# Sheet1.net
KiCad netlist of a schematic drawn in Altium Designer
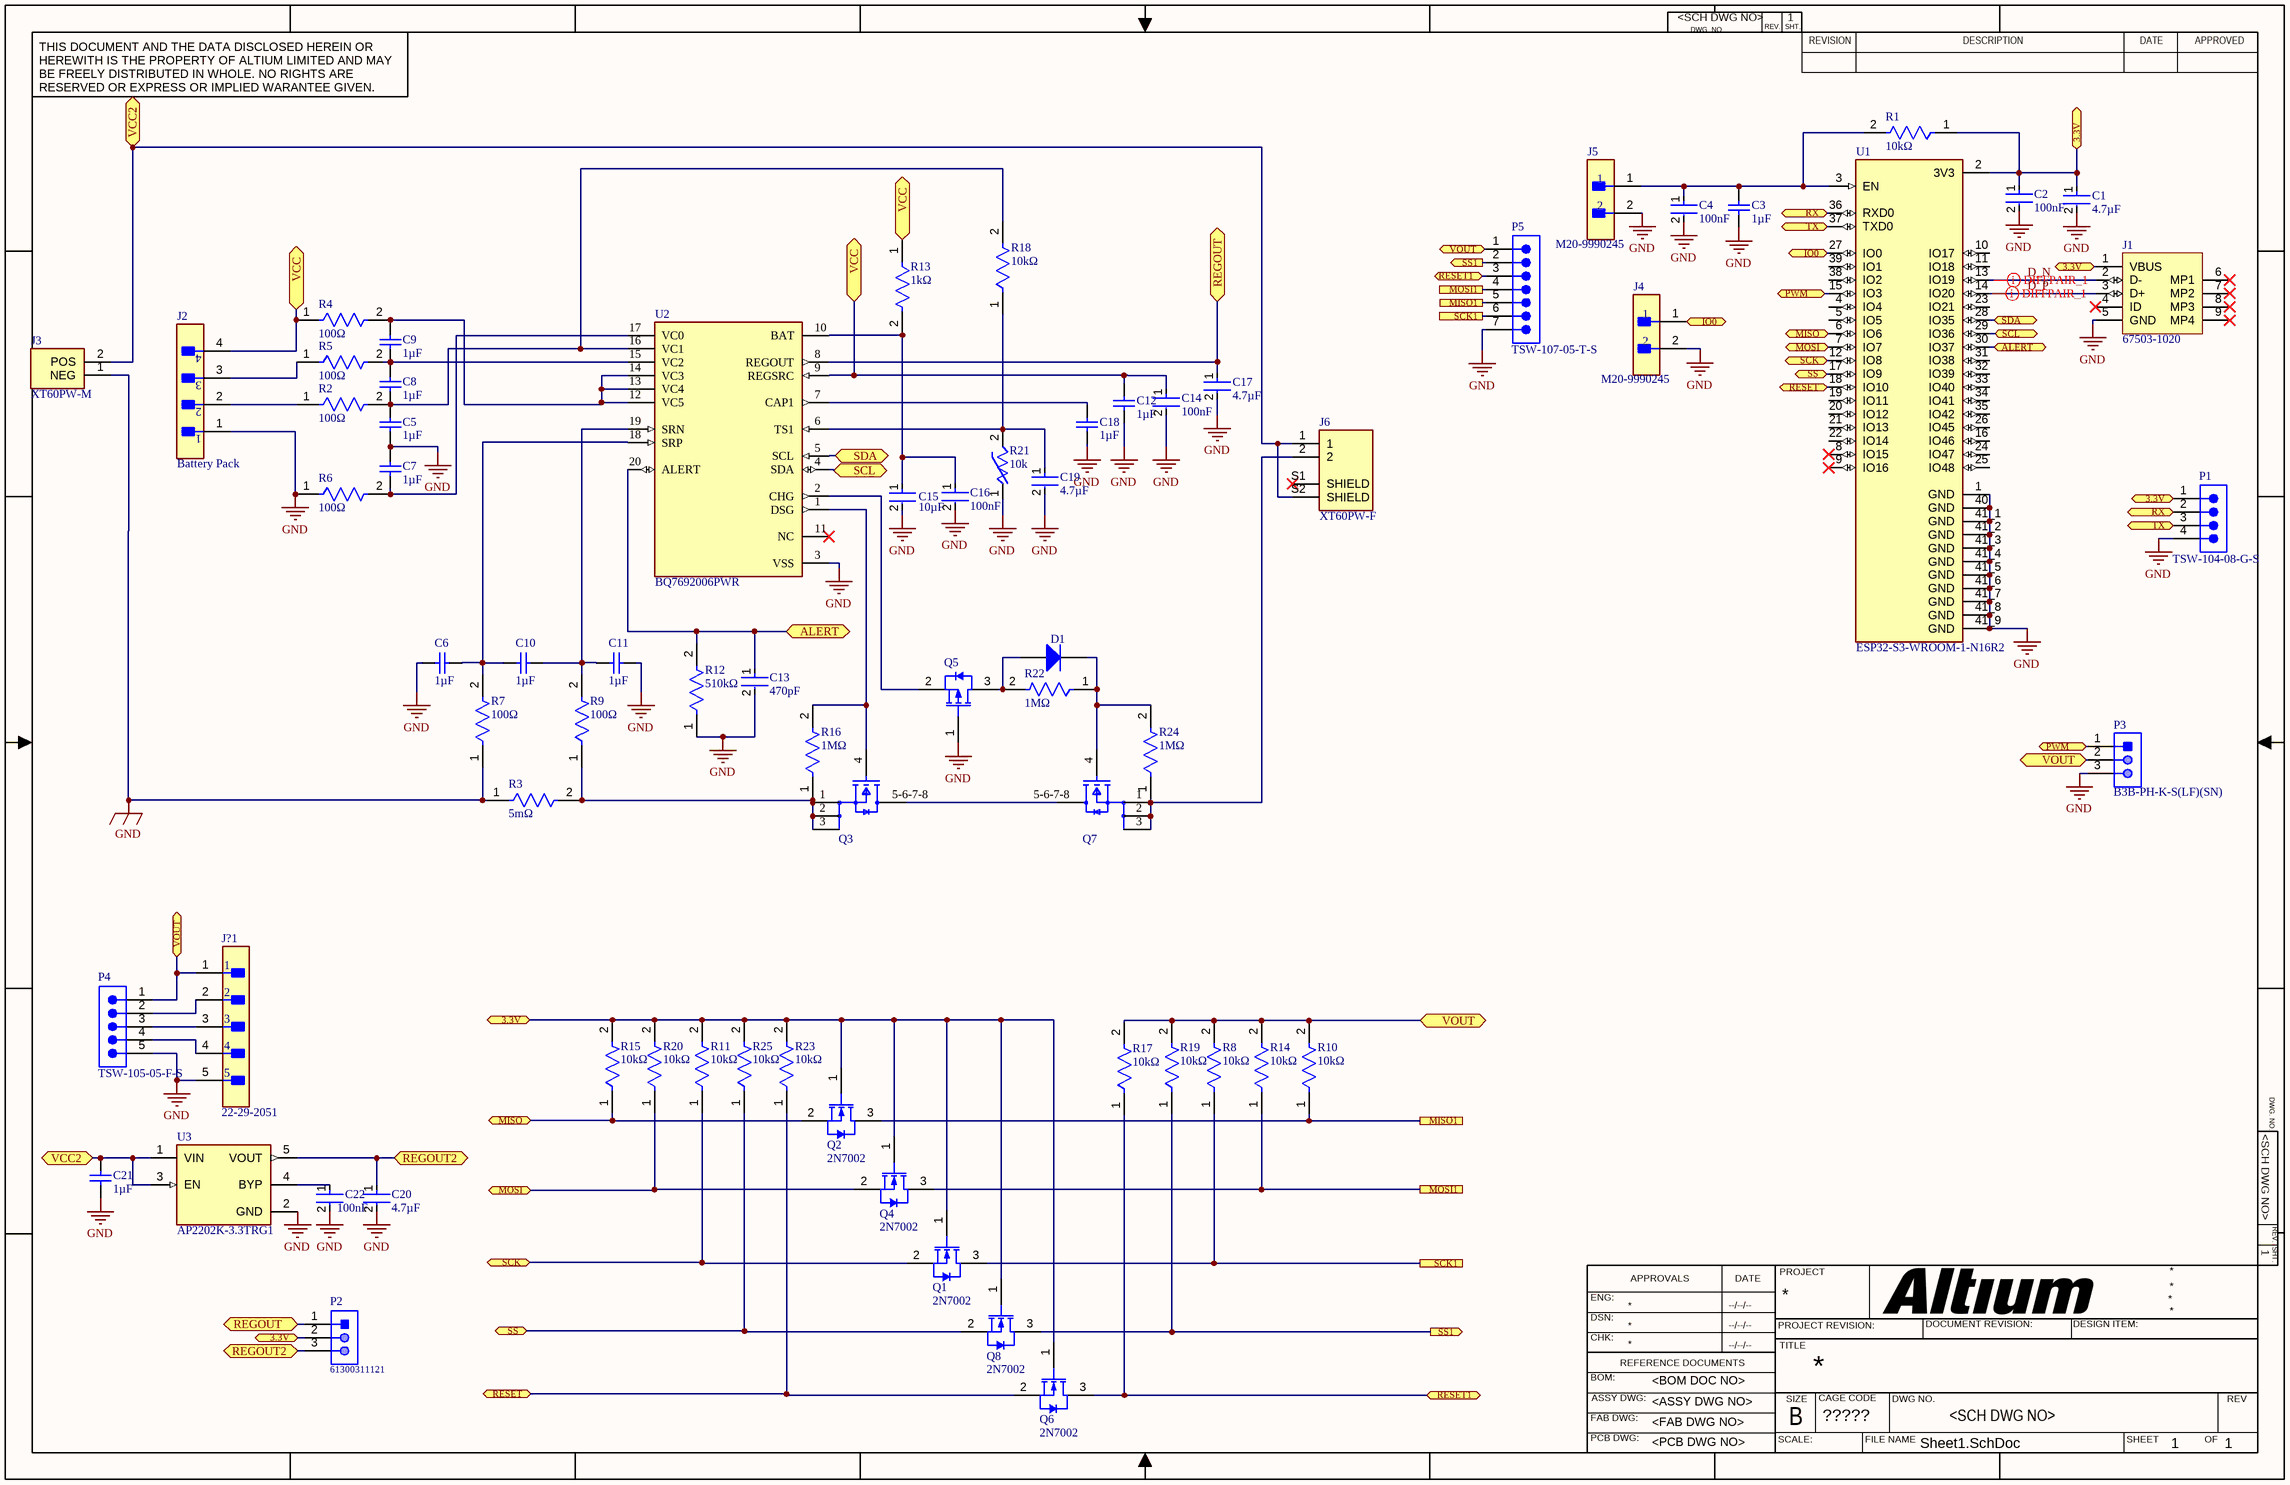
[diagram p0: Sheet1.SchDoc]

(export (version "E")
  (design (tool "Eeschema 10.0.6"))
  (components
    (comp (ref "C1")
      (value "4.7µF")
      (footprint "FP-C2012-125-0_2-IPC_B")
      (description "Multilayer Ceramic Capacitors 4.7μF ±10% 50V X5R SMD 0805")
      (fields (field (name "VOLTAGE") "50V") (field (name "TOLERANCE") "10%"))
      (libsource (lib "Altium Content Vault") (part "b4654b650e69147ec39a6b967a45e02"))
    )
    (comp (ref "C2")
      (value "100nF")
      (footprint "FP-C0603C-CF-MFG")
      (description "CAP CER 0.1UF 50V X7R 0603")
      (fields (field (name "TOLERANCE") "0.1") (field (name "MANUFACTURER") "KEMET"))
      (libsource (lib "Altium Content Vault") (part "b4654b650e69147ec39a6b967a45e02"))
    )
    (comp (ref "C3")
      (value "1µF")
      (footprint "CAPC1608X90X35LL10T15")
      (fields (field (name "MANUFACTURER") "Murata") (field (name "PART NUMBER") "GRM188R61E105KA12D"))
      (libsource (lib "Altium Content Vault") (part "CAP"))
    )
    (comp (ref "C4")
      (value "100nF")
      (footprint "FP-C0603C-CF-MFG")
      (description "CAP CER 0.1UF 50V X7R 0603")
      (fields (field (name "TOLERANCE") "0.1") (field (name "MANUFACTURER") "KEMET"))
      (libsource (lib "Altium Content Vault") (part "b4654b650e69147ec39a6b967a45e02"))
    )
    (comp (ref "C5")
      (value "1µF")
      (footprint "CAPC1608X90X35LL10T15")
      (fields (field (name "MANUFACTURER") "Murata") (field (name "PART NUMBER") "GRM188R61E105KA12D"))
      (libsource (lib "Altium Content Vault") (part "CAP"))
    )
    (comp (ref "C6")
      (value "1µF")
      (footprint "CAPC1608X90X35LL10T15")
      (fields (field (name "MANUFACTURER") "Murata") (field (name "PART NUMBER") "GRM188R61E105KA12D"))
      (libsource (lib "Altium Content Vault") (part "CAP"))
    )
    (comp (ref "C7")
      (value "1µF")
      (footprint "CAPC1608X90X35LL10T15")
      (fields (field (name "MANUFACTURER") "Murata") (field (name "PART NUMBER") "GRM188R61E105KA12D"))
      (libsource (lib "Altium Content Vault") (part "CAP"))
    )
    (comp (ref "C8")
      (value "1µF")
      (footprint "CAPC1608X90X35LL10T15")
      (fields (field (name "MANUFACTURER") "Murata") (field (name "PART NUMBER") "GRM188R61E105KA12D"))
      (libsource (lib "Altium Content Vault") (part "CAP"))
    )
    (comp (ref "C9")
      (value "1µF")
      (footprint "CAPC1608X90X35LL10T15")
      (fields (field (name "MANUFACTURER") "Murata") (field (name "PART NUMBER") "GRM188R61E105KA12D"))
      (libsource (lib "Altium Content Vault") (part "CAP"))
    )
    (comp (ref "C10")
      (value "1µF")
      (footprint "CAPC1608X90X35LL10T15")
      (fields (field (name "MANUFACTURER") "Murata") (field (name "PART NUMBER") "GRM188R61E105KA12D"))
      (libsource (lib "Altium Content Vault") (part "CAP"))
    )
    (comp (ref "C11")
      (value "1µF")
      (footprint "CAPC1608X90X35LL10T15")
      (fields (field (name "MANUFACTURER") "Murata") (field (name "PART NUMBER") "GRM188R61E105KA12D"))
      (libsource (lib "Altium Content Vault") (part "CAP"))
    )
    (comp (ref "C12")
      (value "1µF")
      (footprint "CAPC1608X90X35LL10T15")
      (fields (field (name "MANUFACTURER") "Murata") (field (name "PART NUMBER") "GRM188R61E105KA12D"))
      (libsource (lib "Altium Content Vault") (part "CAP"))
    )
    (comp (ref "C13")
      (value "470pF")
      (footprint "FP-C0603C-CF-MFG")
      (description "CAP CER 470PF 50V X7R 0603")
      (fields (field (name "MANUFACTURER PART NUMBER") "C0603C471K5RACTU") (field (name "TOLERANCE") "0.1"))
      (libsource (lib "Altium Content Vault") (part "b4654b650e69147ec39a6b967a45e02"))
    )
    (comp (ref "C14")
      (value "100nF")
      (footprint "FP-C0603C-CF-MFG")
      (description "CAP CER 0.1UF 50V X7R 0603")
      (fields (field (name "TOLERANCE") "0.1") (field (name "MANUFACTURER") "KEMET"))
      (libsource (lib "Altium Content Vault") (part "b4654b650e69147ec39a6b967a45e02"))
    )
    (comp (ref "C15")
      (value "10µF")
      (footprint "FP-GRM21B-0_15-IPC_C")
      (description "Chip Multilayer Ceramic Capacitors for General Purpose, 0805, 10uF, X5R, 15%, 10%, 25V")
      (fields (field (name "VOLTAGE") "25V") (field (name "TOLERANCE") "10%"))
      (libsource (lib "Altium Content Vault") (part "b4654b650e69147ec39a6b967a45e02"))
    )
    (comp (ref "C16")
      (value "100nF")
      (footprint "FP-C0603C-CF-MFG")
      (description "CAP CER 0.1UF 50V X7R 0603")
      (fields (field (name "TOLERANCE") "0.1") (field (name "MANUFACTURER") "KEMET"))
      (libsource (lib "Altium Content Vault") (part "b4654b650e69147ec39a6b967a45e02"))
    )
    (comp (ref "C17")
      (value "4.7µF")
      (footprint "FP-C2012-125-0_2-IPC_B")
      (description "Multilayer Ceramic Capacitors 4.7μF ±10% 50V X5R SMD 0805")
      (fields (field (name "VOLTAGE") "50V") (field (name "TOLERANCE") "10%"))
      (libsource (lib "Altium Content Vault") (part "b4654b650e69147ec39a6b967a45e02"))
    )
    (comp (ref "C18")
      (value "1µF")
      (footprint "CAPC1608X90X35LL10T15")
      (fields (field (name "MANUFACTURER") "Murata") (field (name "PART NUMBER") "GRM188R61E105KA12D"))
      (libsource (lib "Altium Content Vault") (part "CAP"))
    )
    (comp (ref "C19")
      (value "4.7µF")
      (footprint "FP-C2012-125-0_2-IPC_B")
      (description "Multilayer Ceramic Capacitors 4.7μF ±10% 50V X5R SMD 0805")
      (fields (field (name "VOLTAGE") "50V") (field (name "TOLERANCE") "10%"))
      (libsource (lib "Altium Content Vault") (part "b4654b650e69147ec39a6b967a45e02"))
    )
    (comp (ref "C20")
      (value "4.7µF")
      (footprint "FP-C2012-125-0_2-IPC_B")
      (description "Multilayer Ceramic Capacitors 4.7μF ±10% 50V X5R SMD 0805")
      (fields (field (name "VOLTAGE") "50V") (field (name "TOLERANCE") "10%"))
      (libsource (lib "Altium Content Vault") (part "b4654b650e69147ec39a6b967a45e02"))
    )
    (comp (ref "C21")
      (value "1µF")
      (footprint "CAPC1608X90X35LL10T15")
      (fields (field (name "MANUFACTURER") "Murata") (field (name "PART NUMBER") "GRM188R61E105KA12D"))
      (libsource (lib "Altium Content Vault") (part "CAP"))
    )
    (comp (ref "C22")
      (value "100nF")
      (footprint "FP-C0603C-CF-MFG")
      (description "CAP CER 0.1UF 50V X7R 0603")
      (fields (field (name "TOLERANCE") "0.1") (field (name "MANUFACTURER") "KEMET"))
      (libsource (lib "Altium Content Vault") (part "b4654b650e69147ec39a6b967a45e02"))
    )
    (comp (ref "D1")
      (value "1N4148WS-7-F")
      (footprint "DIOD-SOD323-2-A_V")
      (description "Fast Switching Diode, 75 V, 0.3 A, -65 to 150 degC, 2-Pin SOD323, RoHS, Tape and Reel")
      (libsource (lib "Altium Content Vault") (part "D-AK-2"))
    )
    (comp (ref "J1")
      (value "67503-1020")
      (footprint "MOLX-67503-1020_V")
      (description "USB, MINI, SMD, RA KME04-USBMU03A01")
      (fields (field (name "MANUFACTURER") "Molex"))
      (libsource (lib "Altium Content Vault") (part "MOLX-67503-1020"))
    )
    (comp (ref "J2")
      (value "Battery Pack")
      (footprint "FP-B4B-XH-A_LF_SN-MFG")
      (description "CONN HEADER VERT 4POS 2.5MM")
      (libsource (lib "Altium Content Vault") (part "299a8cea1bdcbc3624fe62c390fa72c"))
    )
    (comp (ref "J3")
      (value "XT60PW-M")
      (footprint "AMASS_XT60PW-M")
      (description "Socket, DC supply, male, PIN: 2")
      (fields (field (name "MF") "AMASS"))
      (libsource (lib "XT60PW-M") (part "XT60PW-M"))
    )
    (comp (ref "J4")
      (value "M20-9990245")
      (footprint "FP-M20-9990245-MFG")
      (description "CONN HEADER VERT 2POS 2.54MM")
      (fields (field (name "VOLTAGE") "50V"))
      (libsource (lib "Altium Content Vault") (part "3bc925449376181038e59eaffc5286c"))
    )
    (comp (ref "J5")
      (value "M20-9990245")
      (footprint "FP-M20-9990245-MFG")
      (description "CONN HEADER VERT 2POS 2.54MM")
      (fields (field (name "VOLTAGE") "50V"))
      (libsource (lib "Altium Content Vault") (part "3bc925449376181038e59eaffc5286c"))
    )
    (comp (ref "J6")
      (value "XT60PW-F")
      (footprint "AMASS_XT60PW-F")
      (description "Socket DC Supply Connector Female")
      (fields (field (name "MF") "AMASS"))
      (libsource (lib "XT60PW-F") (part "XT60PW-F"))
    )
    (comp (ref "J?1")
      (value "22-29-2051")
      (footprint "FP-22-29-2051-MFG")
      (description "2.54MM KK HDR VT FRICLK VRA .5AU")
      (libsource (lib "Altium Content Vault") (part "bf93c07fd2649a848d0ec8585582aab"))
    )
    (comp (ref "P1")
      (value "TSW-104-08-G-S")
      (footprint "SMTC-TSW-104-08-X-S")
      (description "0.025\" SQ Post Header, Through-hole, Vertical, -55 to 125 degC, 2.54 mm Pitch, 4-Pin, Male, RoHS")
      (fields (field (name "MANUFACTURER") "Samtec"))
      (libsource (lib "Altium Content Vault") (part "SMTC-TSW-104-08-X-S"))
    )
    (comp (ref "P2")
      (value "61300311121")
      (footprint "61300311121")
      (description "THT Vertical Pin Header WR-PHD, Pitch 2.54 mm, Single Row, 3 pins")
      (fields (field (name "MANUFACTURER") "Wurth Elektronik") (field (name "PUBLISHER") "WurthElektronik"))
      (libsource (lib "Altium Content Vault") (part "WE-CN-1P-M-R3"))
    )
    (comp (ref "P3")
      (value "B3B-PH-K-S(LF)(SN)")
      (footprint "JST-B3B-PH-K-S-3_V")
      (fields (field (name "MANUFACTURER") "JST"))
      (libsource (lib "Altium Content Vault") (part "CN-1P-M-R3"))
    )
    (comp (ref "P4")
      (value "TSW-105-05-F-S")
      (footprint "SMTC-TSW-105-05-X-S")
      (description "0.025\" SQ Post Header, Through-hole, Vertical, -55 to 125 degC, 2.54 mm Pitch, 5-Pin, Male, RoHS")
      (fields (field (name "MANUFACTURER") "Samtec"))
      (libsource (lib "Altium Content Vault") (part "SMTC-TSW-105-05-X-S"))
    )
    (comp (ref "P5")
      (value "TSW-107-05-T-S")
      (footprint "SMTC-TSW-107-05-X-S")
      (description "0.025\" SQ Post Header, Through-hole, Vertical, -55 to 105 degC, 2.54 mm Pitch, 7-Pin, Male, RoHS")
      (fields (field (name "MANUFACTURER") "Samtec"))
      (libsource (lib "Altium Content Vault") (part "SMTC-TSW-107-05-X-S"))
    )
    (comp (ref "Q1")
      (value "2N7002")
      (footprint "STM-SOT-23-3_V")
      (description "N-channel 60 V, 1.8 Ohm, 0.35 A STripFET(TM) II Power MOSFET, SOT23")
      (fields (field (name "MANUFACTURER") "STMicroelectronics"))
      (libsource (lib "Altium Content Vault") (part "STM-NEMOS-G1S2D3-3"))
    )
    (comp (ref "Q2")
      (value "2N7002")
      (footprint "STM-SOT-23-3_V")
      (description "N-channel 60 V, 1.8 Ohm, 0.35 A STripFET(TM) II Power MOSFET, SOT23")
      (fields (field (name "MANUFACTURER") "STMicroelectronics"))
      (libsource (lib "Altium Content Vault") (part "STM-NEMOS-G1S2D3-3"))
    )
    (comp (ref "Q3")
      (value "AON6362")
      (footprint "FP-DFN5x6_8L_EP1_P-MFG")
      (description "MOSFET N-CH 30V 27A/60A 8DFN")
      (libsource (lib "Altium Content Vault") (part "3daf4540832f5b2d6d8f0ce0a097f6c"))
    )
    (comp (ref "Q4")
      (value "2N7002")
      (footprint "STM-SOT-23-3_V")
      (description "N-channel 60 V, 1.8 Ohm, 0.35 A STripFET(TM) II Power MOSFET, SOT23")
      (fields (field (name "MANUFACTURER") "STMicroelectronics"))
      (libsource (lib "Altium Content Vault") (part "STM-NEMOS-G1S2D3-3"))
    )
    (comp (ref "Q5")
      (value "FDN338P")
      (footprint "FAIR-SSOT3L-3_V")
      (fields (field (name "MANUFACTURER") "Fairchild Semiconductor"))
      (libsource (lib "Altium Content Vault") (part "PEMOS-GSD-3"))
    )
    (comp (ref "Q6")
      (value "2N7002")
      (footprint "STM-SOT-23-3_V")
      (description "N-channel 60 V, 1.8 Ohm, 0.35 A STripFET(TM) II Power MOSFET, SOT23")
      (fields (field (name "MANUFACTURER") "STMicroelectronics"))
      (libsource (lib "Altium Content Vault") (part "STM-NEMOS-G1S2D3-3"))
    )
    (comp (ref "Q7")
      (value "AON6362")
      (footprint "FP-DFN5x6_8L_EP1_P-MFG")
      (description "MOSFET N-CH 30V 27A/60A 8DFN")
      (libsource (lib "Altium Content Vault") (part "3daf4540832f5b2d6d8f0ce0a097f6c"))
    )
    (comp (ref "Q8")
      (value "2N7002")
      (footprint "STM-SOT-23-3_V")
      (description "N-channel 60 V, 1.8 Ohm, 0.35 A STripFET(TM) II Power MOSFET, SOT23")
      (fields (field (name "MANUFACTURER") "STMicroelectronics"))
      (libsource (lib "Altium Content Vault") (part "STM-NEMOS-G1S2D3-3"))
    )
    (comp (ref "R1")
      (value "10kΩ")
      (footprint "FP-CRCW0603-e3-MFG")
      (description "RES Thick Film, 10kΩ, 5%, 0.1W, 200ppm/°C, 0603")
      (fields (field (name "TOLERANCE") "5%"))
      (libsource (lib "Altium Content Vault") (part "1029c3af85768c4190bb7ad29bc67b5"))
    )
    (comp (ref "R2")
      (value "100Ω")
      (footprint "FP-CRCW0603-e3-IPC_A")
      (description "RES Thick Film, 100Ω, 1%, 0.1W, 100ppm/°C, 0603")
      (fields (field (name "TOLERANCE") "1%"))
      (libsource (lib "Altium Content Vault") (part "1029c3af85768c4190bb7ad29bc67b5"))
    )
    (comp (ref "R3")
      (value "5mΩ")
      (footprint "FP-CRE2512-R005-R009-MFG")
      (description "RES 0.005 OHM 1% 3W 2512")
      (fields (field (name "TOLERANCE") "1%"))
      (libsource (lib "Altium Content Vault") (part "1029c3af85768c4190bb7ad29bc67b5"))
    )
    (comp (ref "R4")
      (value "100Ω")
      (footprint "FP-CRCW0603-e3-IPC_A")
      (description "RES Thick Film, 100Ω, 1%, 0.1W, 100ppm/°C, 0603")
      (fields (field (name "TOLERANCE") "1%"))
      (libsource (lib "Altium Content Vault") (part "1029c3af85768c4190bb7ad29bc67b5"))
    )
    (comp (ref "R5")
      (value "100Ω")
      (footprint "FP-CRCW0603-e3-IPC_A")
      (description "RES Thick Film, 100Ω, 1%, 0.1W, 100ppm/°C, 0603")
      (fields (field (name "TOLERANCE") "1%"))
      (libsource (lib "Altium Content Vault") (part "1029c3af85768c4190bb7ad29bc67b5"))
    )
    (comp (ref "R6")
      (value "100Ω")
      (footprint "FP-CRCW0603-e3-IPC_A")
      (description "RES Thick Film, 100Ω, 1%, 0.1W, 100ppm/°C, 0603")
      (fields (field (name "TOLERANCE") "1%"))
      (libsource (lib "Altium Content Vault") (part "1029c3af85768c4190bb7ad29bc67b5"))
    )
    (comp (ref "R7")
      (value "100Ω")
      (footprint "FP-CRCW0603-e3-IPC_A")
      (description "RES Thick Film, 100Ω, 1%, 0.1W, 100ppm/°C, 0603")
      (fields (field (name "TOLERANCE") "1%"))
      (libsource (lib "Altium Content Vault") (part "1029c3af85768c4190bb7ad29bc67b5"))
    )
    (comp (ref "R8")
      (value "10kΩ")
      (footprint "FP-CRCW0603-e3-MFG")
      (description "RES Thick Film, 10kΩ, 5%, 0.1W, 200ppm/°C, 0603")
      (fields (field (name "TOLERANCE") "5%"))
      (libsource (lib "Altium Content Vault") (part "1029c3af85768c4190bb7ad29bc67b5"))
    )
    (comp (ref "R9")
      (value "100Ω")
      (footprint "FP-CRCW0603-e3-IPC_A")
      (description "RES Thick Film, 100Ω, 1%, 0.1W, 100ppm/°C, 0603")
      (fields (field (name "TOLERANCE") "1%"))
      (libsource (lib "Altium Content Vault") (part "1029c3af85768c4190bb7ad29bc67b5"))
    )
    (comp (ref "R10")
      (value "10kΩ")
      (footprint "FP-CRCW0603-e3-MFG")
      (description "RES Thick Film, 10kΩ, 5%, 0.1W, 200ppm/°C, 0603")
      (fields (field (name "TOLERANCE") "5%"))
      (libsource (lib "Altium Content Vault") (part "1029c3af85768c4190bb7ad29bc67b5"))
    )
    (comp (ref "R11")
      (value "10kΩ")
      (footprint "FP-CRCW0603-e3-MFG")
      (description "RES Thick Film, 10kΩ, 5%, 0.1W, 200ppm/°C, 0603")
      (fields (field (name "TOLERANCE") "5%"))
      (libsource (lib "Altium Content Vault") (part "1029c3af85768c4190bb7ad29bc67b5"))
    )
    (comp (ref "R12")
      (value "510kΩ")
      (footprint "FP-CRCW0805-e3-IPC_B")
      (description "RES Thick Film, 510kΩ, 1%, 0.125W, 100ppm/°C, 0805")
      (fields (field (name "TOLERANCE") "1%"))
      (libsource (lib "Altium Content Vault") (part "1029c3af85768c4190bb7ad29bc67b5"))
    )
    (comp (ref "R13")
      (value "1kΩ")
      (footprint "FP-CRCW0603-e3-MFG")
      (description "RES Thick Film, 1kΩ, 1%, 0.1W, 100ppm/°C, 0603")
      (fields (field (name "TOLERANCE") "1%"))
      (libsource (lib "Altium Content Vault") (part "1029c3af85768c4190bb7ad29bc67b5"))
    )
    (comp (ref "R14")
      (value "10kΩ")
      (footprint "FP-CRCW0603-e3-MFG")
      (description "RES Thick Film, 10kΩ, 5%, 0.1W, 200ppm/°C, 0603")
      (fields (field (name "TOLERANCE") "5%"))
      (libsource (lib "Altium Content Vault") (part "1029c3af85768c4190bb7ad29bc67b5"))
    )
    (comp (ref "R15")
      (value "10kΩ")
      (footprint "FP-CRCW0603-e3-MFG")
      (description "RES Thick Film, 10kΩ, 5%, 0.1W, 200ppm/°C, 0603")
      (fields (field (name "TOLERANCE") "5%"))
      (libsource (lib "Altium Content Vault") (part "1029c3af85768c4190bb7ad29bc67b5"))
    )
    (comp (ref "R16")
      (value "1MΩ")
      (footprint "FP-CRCW0603-e3-MFG")
      (description "RES Thick Film, 1MΩ, 1%, 0.1W, 100ppm/°C, 0603")
      (fields (field (name "TOLERANCE") "1%"))
      (libsource (lib "Altium Content Vault") (part "1029c3af85768c4190bb7ad29bc67b5"))
    )
    (comp (ref "R17")
      (value "10kΩ")
      (footprint "FP-CRCW0603-e3-MFG")
      (description "RES Thick Film, 10kΩ, 5%, 0.1W, 200ppm/°C, 0603")
      (fields (field (name "TOLERANCE") "5%"))
      (libsource (lib "Altium Content Vault") (part "1029c3af85768c4190bb7ad29bc67b5"))
    )
    (comp (ref "R18")
      (value "10kΩ")
      (footprint "FP-CRCW0603-e3-MFG")
      (description "RES Thick Film, 10kΩ, 5%, 0.1W, 200ppm/°C, 0603")
      (fields (field (name "TOLERANCE") "5%"))
      (libsource (lib "Altium Content Vault") (part "1029c3af85768c4190bb7ad29bc67b5"))
    )
    (comp (ref "R19")
      (value "10kΩ")
      (footprint "FP-CRCW0603-e3-MFG")
      (description "RES Thick Film, 10kΩ, 5%, 0.1W, 200ppm/°C, 0603")
      (fields (field (name "TOLERANCE") "5%"))
      (libsource (lib "Altium Content Vault") (part "1029c3af85768c4190bb7ad29bc67b5"))
    )
    (comp (ref "R20")
      (value "10kΩ")
      (footprint "FP-CRCW0603-e3-MFG")
      (description "RES Thick Film, 10kΩ, 5%, 0.1W, 200ppm/°C, 0603")
      (fields (field (name "TOLERANCE") "5%"))
      (libsource (lib "Altium Content Vault") (part "1029c3af85768c4190bb7ad29bc67b5"))
    )
    (comp (ref "R21")
      (value "10k")
      (footprint "ThermistorTHT")
      (description "Thermistor NTC 100K Ohm 5% 2-Pin Radial 4190K -5 to -4.5 Bulk")
      (fields
        (field (name "MANUFACTURER") "Vishay BCcomponents")
        (field (name "MANUFACTURER PART NUMBER") "NTCLE100E3104JB0")
      )
      (libsource (lib "Schlib1") (part "NTCLE100E3104JB0"))
    )
    (comp (ref "R22")
      (value "1MΩ")
      (footprint "FP-CRCW0603-e3-MFG")
      (description "RES Thick Film, 1MΩ, 1%, 0.1W, 100ppm/°C, 0603")
      (fields (field (name "TOLERANCE") "1%"))
      (libsource (lib "Altium Content Vault") (part "1029c3af85768c4190bb7ad29bc67b5"))
    )
    (comp (ref "R23")
      (value "10kΩ")
      (footprint "FP-CRCW0603-e3-MFG")
      (description "RES Thick Film, 10kΩ, 5%, 0.1W, 200ppm/°C, 0603")
      (fields (field (name "TOLERANCE") "5%"))
      (libsource (lib "Altium Content Vault") (part "1029c3af85768c4190bb7ad29bc67b5"))
    )
    (comp (ref "R24")
      (value "1MΩ")
      (footprint "FP-CRCW0603-e3-MFG")
      (description "RES Thick Film, 1MΩ, 1%, 0.1W, 100ppm/°C, 0603")
      (fields (field (name "TOLERANCE") "1%"))
      (libsource (lib "Altium Content Vault") (part "1029c3af85768c4190bb7ad29bc67b5"))
    )
    (comp (ref "R25")
      (value "10kΩ")
      (footprint "FP-CRCW0603-e3-MFG")
      (description "RES Thick Film, 10kΩ, 5%, 0.1W, 200ppm/°C, 0603")
      (fields (field (name "TOLERANCE") "5%"))
      (libsource (lib "Altium Content Vault") (part "1029c3af85768c4190bb7ad29bc67b5"))
    )
    (comp (ref "U1")
      (value "ESP32-S3-WROOM-1-N16R2")
      (footprint "XCVR_ESP32-S3-WROOM-1-N16R2")
      (description "Bluetooth, WiFi 802.11b/g/n, Bluetooth v5.0 Transceiver Module 2.4GHz PCB Trace Surface Mount")
      (fields (field (name "MF") "Espressif Systems"))
      (libsource (lib "ESP32-S3-WROOM-1-N16R2") (part "ESP32-S3-WROOM-1-N16R2"))
    )
    (comp (ref "U2")
      (value "BQ7692006PWR")
      (footprint "FP-PW0020A-IPC_B")
      (description "IC BATT MON MULTI 3-5C 20TSSOP")
      (libsource (lib "Altium Content Vault") (part "2737f5332cc9c67ea823bc6cd6859bb"))
    )
    (comp (ref "U3")
      (value "AP2202K-3.3TRG1")
      (footprint "FP-SOT25-MFG")
      (description "IC REG LINEAR 3.3V 150MA SOT23-5")
      (fields
        (field (name "OCTOPART") "https://octopart.com/ap2202k-3.3trg1-diodes+inc.-30954618")
        (field (name "MANUFACTURER") "Diodes Inc.")
      )
      (libsource (lib "Altium Content Vault") (part "006e7a011770a62fb00db70566099d5"))
    )
  )
  (nets
    (net (code "1") (name "/3.3V") (class "Default")
      (node (ref "C1") (pin "1") (pinfunction "1_1") (pintype "passive"))
      (node (ref "C2") (pin "1") (pinfunction "1_1") (pintype "passive"))
      (node (ref "J1") (pin "1") (pinfunction "VBUS_1") (pintype "power_in"))
      (node (ref "P1") (pin "1") (pinfunction "1_1") (pintype "passive"))
      (node (ref "P2") (pin "2") (pinfunction "2_2") (pintype "passive"))
      (node (ref "Q1") (pin "1") (pinfunction "G_1") (pintype "passive"))
      (node (ref "Q2") (pin "1") (pinfunction "G_1") (pintype "passive"))
      (node (ref "Q4") (pin "1") (pinfunction "G_1") (pintype "passive"))
      (node (ref "Q6") (pin "1") (pinfunction "G_1") (pintype "passive"))
      (node (ref "Q8") (pin "1") (pinfunction "G_1") (pintype "passive"))
      (node (ref "R1") (pin "1") (pinfunction "1_1") (pintype "passive"))
      (node (ref "R11") (pin "2") (pinfunction "2_2") (pintype "passive"))
      (node (ref "R15") (pin "2") (pinfunction "2_2") (pintype "passive"))
      (node (ref "R20") (pin "2") (pinfunction "2_2") (pintype "passive"))
      (node (ref "R23") (pin "2") (pinfunction "2_2") (pintype "passive"))
      (node (ref "R25") (pin "2") (pinfunction "2_2") (pintype "passive"))
      (node (ref "U1") (pin "2") (pinfunction "3V3_2") (pintype "power_in"))
    )
    (net (code "2") (name "/ALERT") (class "Default")
      (node (ref "C13") (pin "1") (pinfunction "1_1") (pintype "passive"))
      (node (ref "R12") (pin "2") (pinfunction "2_2") (pintype "passive"))
      (node (ref "U1") (pin "30") (pinfunction "IO37_30") (pintype "bidirectional"))
      (node (ref "U2") (pin "20") (pinfunction "ALERT_20") (pintype "bidirectional"))
    )
    (net (code "3") (name "/D_N") (class "Default")
      (node (ref "J1") (pin "2") (pinfunction "D-_2") (pintype "bidirectional"))
      (node (ref "U1") (pin "13") (pinfunction "IO19_13") (pintype "bidirectional"))
    )
    (net (code "4") (name "/D_P") (class "Default")
      (node (ref "J1") (pin "3") (pinfunction "D+_3") (pintype "bidirectional"))
      (node (ref "U1") (pin "14") (pinfunction "IO20_14") (pintype "bidirectional"))
    )
    (net (code "5") (name "/IO0") (class "Default")
      (node (ref "J4") (pin "1") (pinfunction "1_1") (pintype "passive"))
      (node (ref "U1") (pin "27") (pinfunction "IO0_27") (pintype "bidirectional"))
    )
    (net (code "6") (name "/MISO") (class "Default")
      (node (ref "Q2") (pin "2") (pinfunction "S_2") (pintype "passive"))
      (node (ref "R15") (pin "1") (pinfunction "1_1") (pintype "passive"))
      (node (ref "U1") (pin "6") (pinfunction "IO6_6") (pintype "bidirectional"))
    )
    (net (code "7") (name "/MISO1") (class "Default")
      (node (ref "P5") (pin "5") (pinfunction "5_5") (pintype "passive"))
      (node (ref "Q2") (pin "3") (pinfunction "D_3") (pintype "passive"))
      (node (ref "R10") (pin "1") (pinfunction "1_1") (pintype "passive"))
    )
    (net (code "8") (name "/MOSI") (class "Default")
      (node (ref "Q4") (pin "2") (pinfunction "S_2") (pintype "passive"))
      (node (ref "R20") (pin "1") (pinfunction "1_1") (pintype "passive"))
      (node (ref "U1") (pin "7") (pinfunction "IO7_7") (pintype "bidirectional"))
    )
    (net (code "9") (name "/MOSI1") (class "Default")
      (node (ref "P5") (pin "4") (pinfunction "4_4") (pintype "passive"))
      (node (ref "Q4") (pin "3") (pinfunction "D_3") (pintype "passive"))
      (node (ref "R14") (pin "1") (pinfunction "1_1") (pintype "passive"))
    )
    (net (code "10") (name "/PWM") (class "Default")
      (node (ref "P3") (pin "1") (pinfunction "1_1") (pintype "passive"))
      (node (ref "U1") (pin "15") (pinfunction "IO3_15") (pintype "bidirectional"))
    )
    (net (code "11") (name "/REGOUT") (class "Default")
      (node (ref "C17") (pin "1") (pinfunction "1_1") (pintype "passive"))
      (node (ref "P2") (pin "1") (pinfunction "1_1") (pintype "passive"))
      (node (ref "U2") (pin "8") (pinfunction "REGOUT_8") (pintype "output"))
    )
    (net (code "12") (name "/REGOUT2") (class "Default")
      (node (ref "C20") (pin "1") (pinfunction "1_1") (pintype "passive"))
      (node (ref "P2") (pin "3") (pinfunction "3_3") (pintype "passive"))
      (node (ref "U3") (pin "5") (pinfunction "VOUT_5") (pintype "output"))
    )
    (net (code "13") (name "/RESET") (class "Default")
      (node (ref "Q6") (pin "2") (pinfunction "S_2") (pintype "passive"))
      (node (ref "R23") (pin "1") (pinfunction "1_1") (pintype "passive"))
      (node (ref "U1") (pin "18") (pinfunction "IO10_18") (pintype "bidirectional"))
    )
    (net (code "14") (name "/RESET1") (class "Default")
      (node (ref "P5") (pin "3") (pinfunction "3_3") (pintype "passive"))
      (node (ref "Q6") (pin "3") (pinfunction "D_3") (pintype "passive"))
      (node (ref "R17") (pin "1") (pinfunction "1_1") (pintype "passive"))
    )
    (net (code "15") (name "/RX") (class "Default")
      (node (ref "P1") (pin "2") (pinfunction "2_2") (pintype "passive"))
      (node (ref "U1") (pin "36") (pinfunction "RXD0_36") (pintype "bidirectional"))
    )
    (net (code "16") (name "/SCK") (class "Default")
      (node (ref "Q1") (pin "2") (pinfunction "S_2") (pintype "passive"))
      (node (ref "R11") (pin "1") (pinfunction "1_1") (pintype "passive"))
      (node (ref "U1") (pin "12") (pinfunction "IO8_12") (pintype "bidirectional"))
    )
    (net (code "17") (name "/SCK1") (class "Default")
      (node (ref "P5") (pin "6") (pinfunction "6_6") (pintype "passive"))
      (node (ref "Q1") (pin "3") (pinfunction "D_3") (pintype "passive"))
      (node (ref "R8") (pin "1") (pinfunction "1_1") (pintype "passive"))
    )
    (net (code "18") (name "/SCL") (class "Default")
      (node (ref "U1") (pin "29") (pinfunction "IO36_29") (pintype "bidirectional"))
      (node (ref "U2") (pin "4") (pinfunction "SDA_4") (pintype "bidirectional"))
    )
    (net (code "19") (name "/SDA") (class "Default")
      (node (ref "U1") (pin "28") (pinfunction "IO35_28") (pintype "bidirectional"))
      (node (ref "U2") (pin "5") (pinfunction "SCL_5") (pintype "input"))
    )
    (net (code "20") (name "/SS") (class "Default")
      (node (ref "Q8") (pin "2") (pinfunction "S_2") (pintype "passive"))
      (node (ref "R25") (pin "1") (pinfunction "1_1") (pintype "passive"))
      (node (ref "U1") (pin "17") (pinfunction "IO9_17") (pintype "bidirectional"))
    )
    (net (code "21") (name "/SS1") (class "Default")
      (node (ref "P5") (pin "2") (pinfunction "2_2") (pintype "passive"))
      (node (ref "Q8") (pin "3") (pinfunction "D_3") (pintype "passive"))
      (node (ref "R19") (pin "1") (pinfunction "1_1") (pintype "passive"))
    )
    (net (code "22") (name "/TX") (class "Default")
      (node (ref "P1") (pin "3") (pinfunction "3_3") (pintype "passive"))
      (node (ref "U1") (pin "37") (pinfunction "TXD0_37") (pintype "bidirectional"))
    )
    (net (code "23") (name "/VCC") (class "Default")
      (node (ref "C12") (pin "1") (pinfunction "1_1") (pintype "passive"))
      (node (ref "C14") (pin "1") (pinfunction "1_1") (pintype "passive"))
      (node (ref "J2") (pin "4") (pinfunction "4_4") (pintype "passive"))
      (node (ref "R13") (pin "1") (pinfunction "1_1") (pintype "passive"))
      (node (ref "R4") (pin "1") (pinfunction "1_1") (pintype "passive"))
      (node (ref "U2") (pin "9") (pinfunction "REGSRC_9") (pintype "input"))
    )
    (net (code "24") (name "/VCC2") (class "Default")
      (node (ref "C21") (pin "1") (pinfunction "1_1") (pintype "passive"))
      (node (ref "J3") (pin "2") (pinfunction "POS_2") (pintype "passive"))
      (node (ref "J6") (pin "1") (pinfunction "1_1") (pintype "passive"))
      (node (ref "J6") (pin "S2") (pinfunction "SHIELD_S2") (pintype "passive"))
      (node (ref "U3") (pin "1") (pinfunction "VIN_1") (pintype "power_in"))
      (node (ref "U3") (pin "3") (pinfunction "EN_3") (pintype "input"))
    )
    (net (code "25") (name "/VOUT") (class "Default")
      (node (ref "J?1") (pin "1") (pinfunction "1_1") (pintype "passive"))
      (node (ref "P3") (pin "2") (pinfunction "2_2") (pintype "passive"))
      (node (ref "P4") (pin "1") (pinfunction "1_1") (pintype "passive"))
      (node (ref "P5") (pin "1") (pinfunction "1_1") (pintype "passive"))
      (node (ref "R10") (pin "2") (pinfunction "2_2") (pintype "passive"))
      (node (ref "R14") (pin "2") (pinfunction "2_2") (pintype "passive"))
      (node (ref "R17") (pin "2") (pinfunction "2_2") (pintype "passive"))
      (node (ref "R19") (pin "2") (pinfunction "2_2") (pintype "passive"))
      (node (ref "R8") (pin "2") (pinfunction "2_2") (pintype "passive"))
    )
    (net (code "26") (name "GND") (class "Default")
      (node (ref "C1") (pin "2") (pinfunction "2_2") (pintype "passive"))
      (node (ref "C11") (pin "1") (pinfunction "1_1") (pintype "passive"))
      (node (ref "C12") (pin "2") (pinfunction "2_2") (pintype "passive"))
      (node (ref "C13") (pin "2") (pinfunction "2_2") (pintype "passive"))
      (node (ref "C14") (pin "2") (pinfunction "2_2") (pintype "passive"))
      (node (ref "C15") (pin "2") (pinfunction "2_2") (pintype "passive"))
      (node (ref "C16") (pin "2") (pinfunction "2_2") (pintype "passive"))
      (node (ref "C17") (pin "2") (pinfunction "2_2") (pintype "passive"))
      (node (ref "C18") (pin "2") (pinfunction "2_2") (pintype "passive"))
      (node (ref "C19") (pin "2") (pinfunction "2_2") (pintype "passive"))
      (node (ref "C2") (pin "2") (pinfunction "2_2") (pintype "passive"))
      (node (ref "C20") (pin "2") (pinfunction "2_2") (pintype "passive"))
      (node (ref "C21") (pin "2") (pinfunction "2_2") (pintype "passive"))
      (node (ref "C22") (pin "2") (pinfunction "2_2") (pintype "passive"))
      (node (ref "C3") (pin "2") (pinfunction "2_2") (pintype "passive"))
      (node (ref "C4") (pin "2") (pinfunction "2_2") (pintype "passive"))
      (node (ref "C5") (pin "1") (pinfunction "1_1") (pintype "passive"))
      (node (ref "C6") (pin "2") (pinfunction "2_2") (pintype "passive"))
      (node (ref "C7") (pin "2") (pinfunction "2_2") (pintype "passive"))
      (node (ref "J1") (pin "5") (pinfunction "GND_5") (pintype "power_in"))
      (node (ref "J2") (pin "1") (pinfunction "1_1") (pintype "passive"))
      (node (ref "J3") (pin "1") (pinfunction "NEG_1") (pintype "passive"))
      (node (ref "J4") (pin "2") (pinfunction "2_2") (pintype "passive"))
      (node (ref "J5") (pin "2") (pinfunction "2_2") (pintype "passive"))
      (node (ref "J?1") (pin "5") (pinfunction "5_5") (pintype "passive"))
      (node (ref "P1") (pin "4") (pinfunction "4_4") (pintype "passive"))
      (node (ref "P3") (pin "3") (pinfunction "3_3") (pintype "passive"))
      (node (ref "P4") (pin "5") (pinfunction "5_5") (pintype "passive"))
      (node (ref "P5") (pin "7") (pinfunction "7_7") (pintype "passive"))
      (node (ref "Q5") (pin "1") (pinfunction "GATE_1") (pintype "passive"))
      (node (ref "R12") (pin "1") (pinfunction "1_1") (pintype "passive"))
      (node (ref "R21") (pin "1") (pinfunction "1_1") (pintype "passive"))
      (node (ref "R3") (pin "1") (pinfunction "1_1") (pintype "passive"))
      (node (ref "R6") (pin "1") (pinfunction "1_1") (pintype "passive"))
      (node (ref "R7") (pin "1") (pinfunction "1_1") (pintype "passive"))
      (node (ref "U1") (pin "1") (pinfunction "GND_1") (pintype "power_in"))
      (node (ref "U1") (pin "40") (pinfunction "GND_40") (pintype "power_in"))
      (node (ref "U1") (pin "41_1") (pinfunction "GND_41_1") (pintype "power_in"))
      (node (ref "U1") (pin "41_2") (pinfunction "GND_41_2") (pintype "power_in"))
      (node (ref "U1") (pin "41_3") (pinfunction "GND_41_3") (pintype "power_in"))
      (node (ref "U1") (pin "41_4") (pinfunction "GND_41_4") (pintype "power_in"))
      (node (ref "U1") (pin "41_5") (pinfunction "GND_41_5") (pintype "power_in"))
      (node (ref "U1") (pin "41_6") (pinfunction "GND_41_6") (pintype "power_in"))
      (node (ref "U1") (pin "41_7") (pinfunction "GND_41_7") (pintype "power_in"))
      (node (ref "U1") (pin "41_8") (pinfunction "GND_41_8") (pintype "power_in"))
      (node (ref "U1") (pin "41_9") (pinfunction "GND_41_9") (pintype "power_in"))
      (node (ref "U2") (pin "3") (pinfunction "VSS_3") (pintype "passive"))
      (node (ref "U3") (pin "2") (pinfunction "GND_2") (pintype "power_in"))
    )
    (net (code "27") (name "Net-(D1-A)") (class "Default")
      (node (ref "D1") (pin "1") (pinfunction "A_1") (pintype "passive"))
      (node (ref "Q5") (pin "3") (pinfunction "DRAIN_3") (pintype "passive"))
      (node (ref "R22") (pin "2") (pinfunction "2_2") (pintype "passive"))
    )
    (net (code "28") (name "Net-(D1-K)") (class "Default")
      (node (ref "D1") (pin "2") (pinfunction "K_2") (pintype "passive"))
      (node (ref "Q7") (pin "4") (pinfunction "G_4") (pintype "passive"))
      (node (ref "R22") (pin "1") (pinfunction "1_1") (pintype "passive"))
      (node (ref "R24") (pin "2") (pinfunction "2_2") (pintype "passive"))
    )
    (net (code "29") (name "Net-(J2-Pad2)") (class "Default")
      (node (ref "J2") (pin "2") (pinfunction "2_2") (pintype "passive"))
      (node (ref "R2") (pin "1") (pinfunction "1_1") (pintype "passive"))
    )
    (net (code "30") (name "Net-(J2-Pad3)") (class "Default")
      (node (ref "J2") (pin "3") (pinfunction "3_3") (pintype "passive"))
      (node (ref "R5") (pin "1") (pinfunction "1_1") (pintype "passive"))
    )
    (net (code "31") (name "Net-(J6-Pad2)") (class "Default")
      (node (ref "J6") (pin "2") (pinfunction "2_2") (pintype "passive"))
      (node (ref "Q7") (pin "1") (pinfunction "S_1") (pintype "passive"))
      (node (ref "Q7") (pin "2") (pinfunction "S_2") (pintype "passive"))
      (node (ref "Q7") (pin "3") (pinfunction "S_3") (pintype "passive"))
      (node (ref "R24") (pin "1") (pinfunction "1_1") (pintype "passive"))
    )
    (net (code "32") (name "Net-(J?1-Pad2)") (class "Default")
      (node (ref "J?1") (pin "2") (pinfunction "2_2") (pintype "passive"))
      (node (ref "P4") (pin "2") (pinfunction "2_2") (pintype "passive"))
    )
    (net (code "33") (name "Net-(J?1-Pad3)") (class "Default")
      (node (ref "J?1") (pin "3") (pinfunction "3_3") (pintype "passive"))
      (node (ref "P4") (pin "3") (pinfunction "3_3") (pintype "passive"))
    )
    (net (code "34") (name "Net-(J?1-Pad4)") (class "Default")
      (node (ref "J?1") (pin "4") (pinfunction "4_4") (pintype "passive"))
      (node (ref "P4") (pin "4") (pinfunction "4_4") (pintype "passive"))
    )
    (net (code "35") (name "Net-(Q3-D)") (class "Default")
      (node (ref "Q3") (pin "5-6-7-8") (pinfunction "D_5-6-7-8") (pintype "passive"))
      (node (ref "Q7") (pin "5-6-7-8") (pinfunction "D_5-6-7-8") (pintype "passive"))
    )
    (net (code "36") (name "Net-(Q3-G)") (class "Default")
      (node (ref "Q3") (pin "4") (pinfunction "G_4") (pintype "passive"))
      (node (ref "R16") (pin "2") (pinfunction "2_2") (pintype "passive"))
      (node (ref "U2") (pin "1") (pinfunction "DSG_1") (pintype "output"))
    )
    (net (code "37") (name "Net-(Q3-S-Pad1)") (class "Default")
      (node (ref "Q3") (pin "1") (pinfunction "S_1") (pintype "passive"))
      (node (ref "Q3") (pin "2") (pinfunction "S_2") (pintype "passive"))
      (node (ref "Q3") (pin "3") (pinfunction "S_3") (pintype "passive"))
      (node (ref "R16") (pin "1") (pinfunction "1_1") (pintype "passive"))
      (node (ref "R3") (pin "2") (pinfunction "2_2") (pintype "passive"))
      (node (ref "R9") (pin "1") (pinfunction "1_1") (pintype "passive"))
    )
    (net (code "38") (name "Net-(Q5-SOURCE)") (class "Default")
      (node (ref "Q5") (pin "2") (pinfunction "SOURCE_2") (pintype "passive"))
      (node (ref "U2") (pin "2") (pinfunction "CHG_2") (pintype "output"))
    )
    (net (code "39") (name "Net-(U1-EN)") (class "Default")
      (node (ref "C3") (pin "1") (pinfunction "1_1") (pintype "passive"))
      (node (ref "C4") (pin "1") (pinfunction "1_1") (pintype "passive"))
      (node (ref "J5") (pin "1") (pinfunction "1_1") (pintype "passive"))
      (node (ref "R1") (pin "2") (pinfunction "2_2") (pintype "passive"))
      (node (ref "U1") (pin "3") (pinfunction "EN_3") (pintype "input"))
    )
    (net (code "40") (name "Net-(U2-BAT)") (class "Default")
      (node (ref "C15") (pin "1") (pinfunction "1_1") (pintype "passive"))
      (node (ref "C16") (pin "1") (pinfunction "1_1") (pintype "passive"))
      (node (ref "R13") (pin "2") (pinfunction "2_2") (pintype "passive"))
      (node (ref "U2") (pin "10") (pinfunction "BAT_10") (pintype "power_in"))
    )
    (net (code "41") (name "Net-(U2-CAP1)") (class "Default")
      (node (ref "C18") (pin "1") (pinfunction "1_1") (pintype "passive"))
      (node (ref "U2") (pin "7") (pinfunction "CAP1_7") (pintype "output"))
    )
    (net (code "42") (name "Net-(U2-SRN)") (class "Default")
      (node (ref "C10") (pin "1") (pinfunction "1_1") (pintype "passive"))
      (node (ref "C11") (pin "2") (pinfunction "2_2") (pintype "passive"))
      (node (ref "R9") (pin "2") (pinfunction "2_2") (pintype "passive"))
      (node (ref "U2") (pin "19") (pinfunction "SRN_19") (pintype "input"))
    )
    (net (code "43") (name "Net-(U2-SRP)") (class "Default")
      (node (ref "C10") (pin "2") (pinfunction "2_2") (pintype "passive"))
      (node (ref "C6") (pin "1") (pinfunction "1_1") (pintype "passive"))
      (node (ref "R7") (pin "2") (pinfunction "2_2") (pintype "passive"))
      (node (ref "U2") (pin "18") (pinfunction "SRP_18") (pintype "input"))
    )
    (net (code "44") (name "Net-(U2-TS1)") (class "Default")
      (node (ref "C19") (pin "1") (pinfunction "1_1") (pintype "passive"))
      (node (ref "R18") (pin "1") (pinfunction "1_1") (pintype "passive"))
      (node (ref "R21") (pin "2") (pinfunction "2_2") (pintype "passive"))
      (node (ref "U2") (pin "6") (pinfunction "TS1_6") (pintype "input"))
    )
    (net (code "45") (name "Net-(U2-VC0)") (class "Default")
      (node (ref "C7") (pin "1") (pinfunction "1_1") (pintype "passive"))
      (node (ref "R6") (pin "2") (pinfunction "2_2") (pintype "passive"))
      (node (ref "U2") (pin "17") (pinfunction "VC0_17") (pintype "passive"))
    )
    (net (code "46") (name "Net-(U2-VC1)") (class "Default")
      (node (ref "C5") (pin "2") (pinfunction "2_2") (pintype "passive"))
      (node (ref "C8") (pin "1") (pinfunction "1_1") (pintype "passive"))
      (node (ref "R18") (pin "2") (pinfunction "2_2") (pintype "passive"))
      (node (ref "R2") (pin "2") (pinfunction "2_2") (pintype "passive"))
      (node (ref "U2") (pin "16") (pinfunction "VC1_16") (pintype "passive"))
    )
    (net (code "47") (name "Net-(U2-VC2)") (class "Default")
      (node (ref "C8") (pin "2") (pinfunction "2_2") (pintype "passive"))
      (node (ref "C9") (pin "1") (pinfunction "1_1") (pintype "passive"))
      (node (ref "R5") (pin "2") (pinfunction "2_2") (pintype "passive"))
      (node (ref "U2") (pin "15") (pinfunction "VC2_15") (pintype "passive"))
    )
    (net (code "48") (name "Net-(U2-VC3)") (class "Default")
      (node (ref "C9") (pin "2") (pinfunction "2_2") (pintype "passive"))
      (node (ref "R4") (pin "2") (pinfunction "2_2") (pintype "passive"))
      (node (ref "U2") (pin "12") (pinfunction "VC5_12") (pintype "passive"))
      (node (ref "U2") (pin "13") (pinfunction "VC4_13") (pintype "passive"))
      (node (ref "U2") (pin "14") (pinfunction "VC3_14") (pintype "passive"))
    )
    (net (code "49") (name "Net-(U3-BYP)") (class "Default")
      (node (ref "C22") (pin "1") (pinfunction "1_1") (pintype "passive"))
      (node (ref "U3") (pin "4") (pinfunction "BYP_4") (pintype "passive"))
    )
    (net (code "50") (name "unconnected-(J1-ID-Pad4)") (class "Default")
      (node (ref "J1") (pin "4") (pinfunction "ID_4") (pintype "passive+no_connect"))
    )
    (net (code "51") (name "unconnected-(J1-MP1-Pad6)") (class "Default")
      (node (ref "J1") (pin "6") (pinfunction "MP1_6") (pintype "passive+no_connect"))
    )
    (net (code "52") (name "unconnected-(J1-MP2-Pad7)") (class "Default")
      (node (ref "J1") (pin "7") (pinfunction "MP2_7") (pintype "passive+no_connect"))
    )
    (net (code "53") (name "unconnected-(J1-MP3-Pad8)") (class "Default")
      (node (ref "J1") (pin "8") (pinfunction "MP3_8") (pintype "passive+no_connect"))
    )
    (net (code "54") (name "unconnected-(J1-MP4-Pad9)") (class "Default")
      (node (ref "J1") (pin "9") (pinfunction "MP4_9") (pintype "passive+no_connect"))
    )
    (net (code "55") (name "unconnected-(J6-SHIELD-PadS1)") (class "Default")
      (node (ref "J6") (pin "S1") (pinfunction "SHIELD_S1") (pintype "passive+no_connect"))
    )
    (net (code "56") (name "unconnected-(U1-IO1-Pad39)") (class "Default")
      (node (ref "U1") (pin "39") (pinfunction "IO1_39") (pintype "bidirectional"))
    )
    (net (code "57") (name "unconnected-(U1-IO2-Pad38)") (class "Default")
      (node (ref "U1") (pin "38") (pinfunction "IO2_38") (pintype "bidirectional"))
    )
    (net (code "58") (name "unconnected-(U1-IO4-Pad4)") (class "Default")
      (node (ref "U1") (pin "4") (pinfunction "IO4_4") (pintype "bidirectional"))
    )
    (net (code "59") (name "unconnected-(U1-IO5-Pad5)") (class "Default")
      (node (ref "U1") (pin "5") (pinfunction "IO5_5") (pintype "bidirectional"))
    )
    (net (code "60") (name "unconnected-(U1-IO11-Pad19)") (class "Default")
      (node (ref "U1") (pin "19") (pinfunction "IO11_19") (pintype "bidirectional"))
    )
    (net (code "61") (name "unconnected-(U1-IO12-Pad20)") (class "Default")
      (node (ref "U1") (pin "20") (pinfunction "IO12_20") (pintype "bidirectional"))
    )
    (net (code "62") (name "unconnected-(U1-IO13-Pad21)") (class "Default")
      (node (ref "U1") (pin "21") (pinfunction "IO13_21") (pintype "bidirectional"))
    )
    (net (code "63") (name "unconnected-(U1-IO14-Pad22)") (class "Default")
      (node (ref "U1") (pin "22") (pinfunction "IO14_22") (pintype "bidirectional"))
    )
    (net (code "64") (name "unconnected-(U1-IO15-Pad8)") (class "Default")
      (node (ref "U1") (pin "8") (pinfunction "IO15_8") (pintype "bidirectional+no_connect"))
    )
    (net (code "65") (name "unconnected-(U1-IO16-Pad9)") (class "Default")
      (node (ref "U1") (pin "9") (pinfunction "IO16_9") (pintype "bidirectional+no_connect"))
    )
    (net (code "66") (name "unconnected-(U1-IO17-Pad10)") (class "Default")
      (node (ref "U1") (pin "10") (pinfunction "IO17_10") (pintype "bidirectional"))
    )
    (net (code "67") (name "unconnected-(U1-IO18-Pad11)") (class "Default")
      (node (ref "U1") (pin "11") (pinfunction "IO18_11") (pintype "bidirectional"))
    )
    (net (code "68") (name "unconnected-(U1-IO21-Pad23)") (class "Default")
      (node (ref "U1") (pin "23") (pinfunction "IO21_23") (pintype "bidirectional"))
    )
    (net (code "69") (name "unconnected-(U1-IO38-Pad31)") (class "Default")
      (node (ref "U1") (pin "31") (pinfunction "IO38_31") (pintype "bidirectional"))
    )
    (net (code "70") (name "unconnected-(U1-IO39-Pad32)") (class "Default")
      (node (ref "U1") (pin "32") (pinfunction "IO39_32") (pintype "bidirectional"))
    )
    (net (code "71") (name "unconnected-(U1-IO40-Pad33)") (class "Default")
      (node (ref "U1") (pin "33") (pinfunction "IO40_33") (pintype "bidirectional"))
    )
    (net (code "72") (name "unconnected-(U1-IO41-Pad34)") (class "Default")
      (node (ref "U1") (pin "34") (pinfunction "IO41_34") (pintype "bidirectional"))
    )
    (net (code "73") (name "unconnected-(U1-IO42-Pad35)") (class "Default")
      (node (ref "U1") (pin "35") (pinfunction "IO42_35") (pintype "bidirectional"))
    )
    (net (code "74") (name "unconnected-(U1-IO45-Pad26)") (class "Default")
      (node (ref "U1") (pin "26") (pinfunction "IO45_26") (pintype "bidirectional"))
    )
    (net (code "75") (name "unconnected-(U1-IO46-Pad16)") (class "Default")
      (node (ref "U1") (pin "16") (pinfunction "IO46_16") (pintype "bidirectional"))
    )
    (net (code "76") (name "unconnected-(U1-IO47-Pad24)") (class "Default")
      (node (ref "U1") (pin "24") (pinfunction "IO47_24") (pintype "bidirectional"))
    )
    (net (code "77") (name "unconnected-(U1-IO48-Pad25)") (class "Default")
      (node (ref "U1") (pin "25") (pinfunction "IO48_25") (pintype "bidirectional"))
    )
    (net (code "78") (name "unconnected-(U2-NC-Pad11)") (class "Default")
      (node (ref "U2") (pin "11") (pinfunction "NC_11") (pintype "passive+no_connect"))
    )
  )
)
